# avrmf.net
KiCad netlist of a schematic drawn in EAGLE
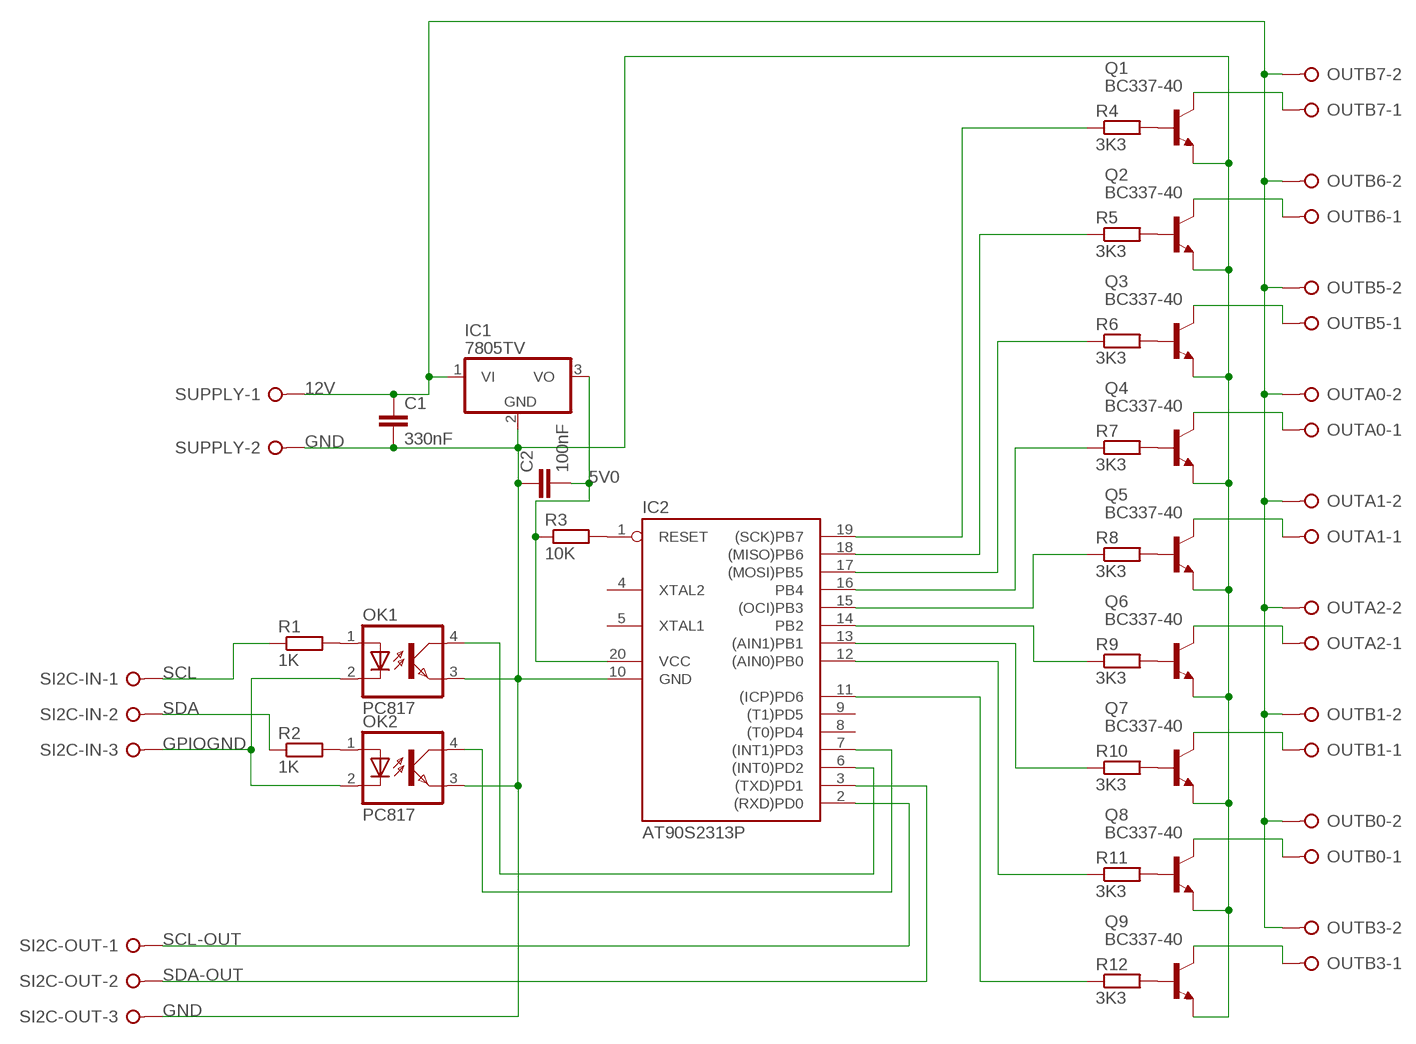
[diagram p0: schematic, sheet 1]

(export (version "E")
  (design (tool "Eeschema 10.0.6"))
  (components
    (comp (ref "C1")
      (value "330nF")
      (footprint "eagle-import:C2.5-3")
      (libsource (lib "eagle-import") (part "C2,5-3"))
    )
    (comp (ref "C2")
      (value "100nF")
      (footprint "eagle-import:C2.5-3")
      (libsource (lib "eagle-import") (part "C2,5-3"))
    )
    (comp (ref "IC1")
      (value "7805TV")
      (footprint "eagle-import:TO220V")
      (libsource (lib "eagle-import") (part "78TV05"))
    )
    (comp (ref "IC2")
      (value "AT90S2313P")
      (footprint "eagle-import:DIL20")
      (libsource (lib "eagle-import") (part "AT90S2313P"))
    )
    (comp (ref "OK1")
      (value "PC817")
      (footprint "eagle-import:DIL04")
      (fields (field (name "MPN") "PC817X4J000F"))
      (libsource (lib "eagle-import") (part "PC817"))
    )
    (comp (ref "OK2")
      (value "PC817")
      (footprint "eagle-import:DIL04")
      (fields (field (name "MPN") "PC817X4J000F"))
      (libsource (lib "eagle-import") (part "PC817"))
    )
    (comp (ref "OUTA0")
      (value "W237-02P")
      (footprint "eagle-import:W237-132")
      (libsource (lib "eagle-import") (part "W237-02P"))
    )
    (comp (ref "OUTA1")
      (value "W237-02P")
      (footprint "eagle-import:W237-132")
      (libsource (lib "eagle-import") (part "W237-02P"))
    )
    (comp (ref "OUTA2")
      (value "W237-02P")
      (footprint "eagle-import:W237-132")
      (libsource (lib "eagle-import") (part "W237-02P"))
    )
    (comp (ref "OUTB0")
      (value "W237-02P")
      (footprint "eagle-import:W237-132")
      (libsource (lib "eagle-import") (part "W237-02P"))
    )
    (comp (ref "OUTB1")
      (value "W237-02P")
      (footprint "eagle-import:W237-132")
      (libsource (lib "eagle-import") (part "W237-02P"))
    )
    (comp (ref "OUTB3")
      (value "W237-02P")
      (footprint "eagle-import:W237-132")
      (libsource (lib "eagle-import") (part "W237-02P"))
    )
    (comp (ref "OUTB5")
      (value "W237-02P")
      (footprint "eagle-import:W237-132")
      (libsource (lib "eagle-import") (part "W237-02P"))
    )
    (comp (ref "OUTB6")
      (value "W237-02P")
      (footprint "eagle-import:W237-132")
      (libsource (lib "eagle-import") (part "W237-02P"))
    )
    (comp (ref "OUTB7")
      (value "W237-02P")
      (footprint "eagle-import:W237-132")
      (libsource (lib "eagle-import") (part "W237-02P"))
    )
    (comp (ref "Q1")
      (value "BC337-40")
      (footprint "eagle-import:TO92")
      (libsource (lib "eagle-import") (part "BC337-40"))
    )
    (comp (ref "Q2")
      (value "BC337-40")
      (footprint "eagle-import:TO92")
      (libsource (lib "eagle-import") (part "BC337-40"))
    )
    (comp (ref "Q3")
      (value "BC337-40")
      (footprint "eagle-import:TO92")
      (libsource (lib "eagle-import") (part "BC337-40"))
    )
    (comp (ref "Q4")
      (value "BC337-40")
      (footprint "eagle-import:TO92")
      (libsource (lib "eagle-import") (part "BC337-40"))
    )
    (comp (ref "Q5")
      (value "BC337-40")
      (footprint "eagle-import:TO92")
      (libsource (lib "eagle-import") (part "BC337-40"))
    )
    (comp (ref "Q6")
      (value "BC337-40")
      (footprint "eagle-import:TO92")
      (libsource (lib "eagle-import") (part "BC337-40"))
    )
    (comp (ref "Q7")
      (value "BC337-40")
      (footprint "eagle-import:TO92")
      (libsource (lib "eagle-import") (part "BC337-40"))
    )
    (comp (ref "Q8")
      (value "BC337-40")
      (footprint "eagle-import:TO92")
      (libsource (lib "eagle-import") (part "BC337-40"))
    )
    (comp (ref "Q9")
      (value "BC337-40")
      (footprint "eagle-import:TO92")
      (libsource (lib "eagle-import") (part "BC337-40"))
    )
    (comp (ref "R1")
      (value "1K")
      (footprint "eagle-import:0207_10")
      (libsource (lib "eagle-import") (part "R-EU_0207/10"))
    )
    (comp (ref "R2")
      (value "1K")
      (footprint "eagle-import:0207_10")
      (libsource (lib "eagle-import") (part "R-EU_0207/10"))
    )
    (comp (ref "R3")
      (value "10K")
      (footprint "eagle-import:0207_10")
      (libsource (lib "eagle-import") (part "R-EU_0207/10"))
    )
    (comp (ref "R4")
      (value "3K3")
      (footprint "eagle-import:0207_10")
      (libsource (lib "eagle-import") (part "R-EU_0207/10"))
    )
    (comp (ref "R5")
      (value "3K3")
      (footprint "eagle-import:0207_10")
      (libsource (lib "eagle-import") (part "R-EU_0207/10"))
    )
    (comp (ref "R6")
      (value "3K3")
      (footprint "eagle-import:0207_10")
      (libsource (lib "eagle-import") (part "R-EU_0207/10"))
    )
    (comp (ref "R7")
      (value "3K3")
      (footprint "eagle-import:0207_10")
      (libsource (lib "eagle-import") (part "R-EU_0207/10"))
    )
    (comp (ref "R8")
      (value "3K3")
      (footprint "eagle-import:0207_10")
      (libsource (lib "eagle-import") (part "R-EU_0207/10"))
    )
    (comp (ref "R9")
      (value "3K3")
      (footprint "eagle-import:0207_10")
      (libsource (lib "eagle-import") (part "R-EU_0207/10"))
    )
    (comp (ref "R10")
      (value "3K3")
      (footprint "eagle-import:0207_10")
      (libsource (lib "eagle-import") (part "R-EU_0207/10"))
    )
    (comp (ref "R11")
      (value "3K3")
      (footprint "eagle-import:0207_10")
      (libsource (lib "eagle-import") (part "R-EU_0207/10"))
    )
    (comp (ref "R12")
      (value "3K3")
      (footprint "eagle-import:0207_10")
      (libsource (lib "eagle-import") (part "R-EU_0207/10"))
    )
    (comp (ref "SI2C-IN")
      (value "W237-3E")
      (footprint "eagle-import:W237-3E")
      (libsource (lib "eagle-import") (part "W237-3E"))
    )
    (comp (ref "SI2C-OUT")
      (value "W237-3E")
      (footprint "eagle-import:W237-3E")
      (libsource (lib "eagle-import") (part "W237-3E"))
    )
    (comp (ref "SUPPLY")
      (value "W237-02P")
      (footprint "eagle-import:W237-132")
      (libsource (lib "eagle-import") (part "W237-02P"))
    )
  )
  (nets
    (net (code "1") (name "/5V0") (class "Default")
      (node (ref "C2") (pin "2") (pinfunction "2_2") (pintype "passive"))
      (node (ref "IC1") (pin "3") (pinfunction "VO_3") (pintype "passive"))
      (node (ref "IC2") (pin "20") (pinfunction "VCC_20") (pintype "power_in"))
      (node (ref "R3") (pin "1") (pinfunction "1_1") (pintype "passive"))
    )
    (net (code "2") (name "/12V") (class "Default")
      (node (ref "C1") (pin "1") (pinfunction "1_1") (pintype "passive"))
      (node (ref "IC1") (pin "1") (pinfunction "VI_1") (pintype "input"))
      (node (ref "OUTA0") (pin "2") (pinfunction "KL_2") (pintype "passive"))
      (node (ref "OUTA1") (pin "2") (pinfunction "KL_2") (pintype "passive"))
      (node (ref "OUTA2") (pin "2") (pinfunction "KL_2") (pintype "passive"))
      (node (ref "OUTB0") (pin "2") (pinfunction "KL_2") (pintype "passive"))
      (node (ref "OUTB1") (pin "2") (pinfunction "KL_2") (pintype "passive"))
      (node (ref "OUTB3") (pin "2") (pinfunction "KL_2") (pintype "passive"))
      (node (ref "OUTB5") (pin "2") (pinfunction "KL_2") (pintype "passive"))
      (node (ref "OUTB6") (pin "2") (pinfunction "KL_2") (pintype "passive"))
      (node (ref "OUTB7") (pin "2") (pinfunction "KL_2") (pintype "passive"))
      (node (ref "SUPPLY") (pin "1") (pinfunction "KL_1") (pintype "passive"))
    )
    (net (code "3") (name "/GND") (class "Default")
      (node (ref "C1") (pin "2") (pinfunction "2_2") (pintype "passive"))
      (node (ref "C2") (pin "1") (pinfunction "1_1") (pintype "passive"))
      (node (ref "IC1") (pin "2") (pinfunction "GND_2") (pintype "passive"))
      (node (ref "IC2") (pin "10") (pinfunction "GND_10") (pintype "power_in"))
      (node (ref "OK1") (pin "3") (pinfunction "EMIT_3") (pintype "passive"))
      (node (ref "OK2") (pin "3") (pinfunction "EMIT_3") (pintype "passive"))
      (node (ref "Q1") (pin "1") (pinfunction "E_1") (pintype "passive"))
      (node (ref "Q2") (pin "1") (pinfunction "E_1") (pintype "passive"))
      (node (ref "Q3") (pin "1") (pinfunction "E_1") (pintype "passive"))
      (node (ref "Q4") (pin "1") (pinfunction "E_1") (pintype "passive"))
      (node (ref "Q5") (pin "1") (pinfunction "E_1") (pintype "passive"))
      (node (ref "Q6") (pin "1") (pinfunction "E_1") (pintype "passive"))
      (node (ref "Q7") (pin "1") (pinfunction "E_1") (pintype "passive"))
      (node (ref "Q8") (pin "1") (pinfunction "E_1") (pintype "passive"))
      (node (ref "Q9") (pin "1") (pinfunction "E_1") (pintype "passive"))
      (node (ref "SI2C-OUT") (pin "3") (pinfunction "KL_3") (pintype "passive"))
      (node (ref "SUPPLY") (pin "2") (pinfunction "KL_2") (pintype "passive"))
    )
    (net (code "4") (name "/GPIOGND") (class "Default")
      (node (ref "OK1") (pin "2") (pinfunction "C_2") (pintype "passive"))
      (node (ref "OK2") (pin "2") (pinfunction "C_2") (pintype "passive"))
      (node (ref "SI2C-IN") (pin "3") (pinfunction "KL_3") (pintype "passive"))
    )
    (net (code "5") (name "/SCL") (class "Default")
      (node (ref "R1") (pin "1") (pinfunction "1_1") (pintype "passive"))
      (node (ref "SI2C-IN") (pin "1") (pinfunction "KL_1") (pintype "passive"))
    )
    (net (code "6") (name "/SCL-OUT") (class "Default")
      (node (ref "IC2") (pin "2") (pinfunction "(RXD)PD0_2") (pintype "bidirectional"))
      (node (ref "SI2C-OUT") (pin "1") (pinfunction "KL_1") (pintype "passive"))
    )
    (net (code "7") (name "/SDA") (class "Default")
      (node (ref "R2") (pin "1") (pinfunction "1_1") (pintype "passive"))
      (node (ref "SI2C-IN") (pin "2") (pinfunction "KL_2") (pintype "passive"))
    )
    (net (code "8") (name "/SDA-OUT") (class "Default")
      (node (ref "IC2") (pin "3") (pinfunction "(TXD)PD1_3") (pintype "bidirectional"))
      (node (ref "SI2C-OUT") (pin "2") (pinfunction "KL_2") (pintype "passive"))
    )
    (net (code "9") (name "Net-(IC2-(AIN0)PB0)") (class "Default")
      (node (ref "IC2") (pin "12") (pinfunction "(AIN0)PB0_12") (pintype "bidirectional"))
      (node (ref "R11") (pin "1") (pinfunction "1_1") (pintype "passive"))
    )
    (net (code "10") (name "Net-(IC2-(AIN1)PB1)") (class "Default")
      (node (ref "IC2") (pin "13") (pinfunction "(AIN1)PB1_13") (pintype "bidirectional"))
      (node (ref "R10") (pin "1") (pinfunction "1_1") (pintype "passive"))
    )
    (net (code "11") (name "Net-(IC2-(ICP)PD6)") (class "Default")
      (node (ref "IC2") (pin "11") (pinfunction "(ICP)PD6_11") (pintype "bidirectional"))
      (node (ref "R12") (pin "1") (pinfunction "1_1") (pintype "passive"))
    )
    (net (code "12") (name "Net-(IC2-(INT0)PD2)") (class "Default")
      (node (ref "IC2") (pin "6") (pinfunction "(INT0)PD2_6") (pintype "bidirectional"))
      (node (ref "OK1") (pin "4") (pinfunction "COL_4") (pintype "passive"))
    )
    (net (code "13") (name "Net-(IC2-(INT1)PD3)") (class "Default")
      (node (ref "IC2") (pin "7") (pinfunction "(INT1)PD3_7") (pintype "bidirectional"))
      (node (ref "OK2") (pin "4") (pinfunction "COL_4") (pintype "passive"))
    )
    (net (code "14") (name "Net-(IC2-(MISO)PB6)") (class "Default")
      (node (ref "IC2") (pin "18") (pinfunction "(MISO)PB6_18") (pintype "bidirectional"))
      (node (ref "R5") (pin "1") (pinfunction "1_1") (pintype "passive"))
    )
    (net (code "15") (name "Net-(IC2-(MOSI)PB5)") (class "Default")
      (node (ref "IC2") (pin "17") (pinfunction "(MOSI)PB5_17") (pintype "bidirectional"))
      (node (ref "R6") (pin "1") (pinfunction "1_1") (pintype "passive"))
    )
    (net (code "16") (name "Net-(IC2-(OCI)PB3)") (class "Default")
      (node (ref "IC2") (pin "15") (pinfunction "(OCI)PB3_15") (pintype "bidirectional"))
      (node (ref "R8") (pin "1") (pinfunction "1_1") (pintype "passive"))
    )
    (net (code "17") (name "Net-(IC2-(SCK)PB7)") (class "Default")
      (node (ref "IC2") (pin "19") (pinfunction "(SCK)PB7_19") (pintype "bidirectional"))
      (node (ref "R4") (pin "1") (pinfunction "1_1") (pintype "passive"))
    )
    (net (code "18") (name "Net-(IC2-PB2)") (class "Default")
      (node (ref "IC2") (pin "14") (pinfunction "PB2_14") (pintype "bidirectional"))
      (node (ref "R9") (pin "1") (pinfunction "1_1") (pintype "passive"))
    )
    (net (code "19") (name "Net-(IC2-PB4)") (class "Default")
      (node (ref "IC2") (pin "16") (pinfunction "PB4_16") (pintype "bidirectional"))
      (node (ref "R7") (pin "1") (pinfunction "1_1") (pintype "passive"))
    )
    (net (code "20") (name "Net-(IC2-RESET)") (class "Default")
      (node (ref "IC2") (pin "1") (pinfunction "RESET_1") (pintype "bidirectional"))
      (node (ref "R3") (pin "2") (pinfunction "2_2") (pintype "passive"))
    )
    (net (code "21") (name "Net-(OK1-A)") (class "Default")
      (node (ref "OK1") (pin "1") (pinfunction "A_1") (pintype "passive"))
      (node (ref "R1") (pin "2") (pinfunction "2_2") (pintype "passive"))
    )
    (net (code "22") (name "Net-(OK2-A)") (class "Default")
      (node (ref "OK2") (pin "1") (pinfunction "A_1") (pintype "passive"))
      (node (ref "R2") (pin "2") (pinfunction "2_2") (pintype "passive"))
    )
    (net (code "23") (name "Net-(OUTA0A-KL)") (class "Default")
      (node (ref "OUTA0") (pin "1") (pinfunction "KL_1") (pintype "passive"))
      (node (ref "Q4") (pin "3") (pinfunction "C_3") (pintype "passive"))
    )
    (net (code "24") (name "Net-(OUTA1A-KL)") (class "Default")
      (node (ref "OUTA1") (pin "1") (pinfunction "KL_1") (pintype "passive"))
      (node (ref "Q5") (pin "3") (pinfunction "C_3") (pintype "passive"))
    )
    (net (code "25") (name "Net-(OUTA2A-KL)") (class "Default")
      (node (ref "OUTA2") (pin "1") (pinfunction "KL_1") (pintype "passive"))
      (node (ref "Q6") (pin "3") (pinfunction "C_3") (pintype "passive"))
    )
    (net (code "26") (name "Net-(OUTB0A-KL)") (class "Default")
      (node (ref "OUTB0") (pin "1") (pinfunction "KL_1") (pintype "passive"))
      (node (ref "Q8") (pin "3") (pinfunction "C_3") (pintype "passive"))
    )
    (net (code "27") (name "Net-(OUTB1A-KL)") (class "Default")
      (node (ref "OUTB1") (pin "1") (pinfunction "KL_1") (pintype "passive"))
      (node (ref "Q7") (pin "3") (pinfunction "C_3") (pintype "passive"))
    )
    (net (code "28") (name "Net-(OUTB3A-KL)") (class "Default")
      (node (ref "OUTB3") (pin "1") (pinfunction "KL_1") (pintype "passive"))
      (node (ref "Q9") (pin "3") (pinfunction "C_3") (pintype "passive"))
    )
    (net (code "29") (name "Net-(OUTB5A-KL)") (class "Default")
      (node (ref "OUTB5") (pin "1") (pinfunction "KL_1") (pintype "passive"))
      (node (ref "Q3") (pin "3") (pinfunction "C_3") (pintype "passive"))
    )
    (net (code "30") (name "Net-(OUTB6A-KL)") (class "Default")
      (node (ref "OUTB6") (pin "1") (pinfunction "KL_1") (pintype "passive"))
      (node (ref "Q2") (pin "3") (pinfunction "C_3") (pintype "passive"))
    )
    (net (code "31") (name "Net-(OUTB7A-KL)") (class "Default")
      (node (ref "OUTB7") (pin "1") (pinfunction "KL_1") (pintype "passive"))
      (node (ref "Q1") (pin "3") (pinfunction "C_3") (pintype "passive"))
    )
    (net (code "32") (name "Net-(Q1-B)") (class "Default")
      (node (ref "Q1") (pin "2") (pinfunction "B_2") (pintype "passive"))
      (node (ref "R4") (pin "2") (pinfunction "2_2") (pintype "passive"))
    )
    (net (code "33") (name "Net-(Q2-B)") (class "Default")
      (node (ref "Q2") (pin "2") (pinfunction "B_2") (pintype "passive"))
      (node (ref "R5") (pin "2") (pinfunction "2_2") (pintype "passive"))
    )
    (net (code "34") (name "Net-(Q3-B)") (class "Default")
      (node (ref "Q3") (pin "2") (pinfunction "B_2") (pintype "passive"))
      (node (ref "R6") (pin "2") (pinfunction "2_2") (pintype "passive"))
    )
    (net (code "35") (name "Net-(Q4-B)") (class "Default")
      (node (ref "Q4") (pin "2") (pinfunction "B_2") (pintype "passive"))
      (node (ref "R7") (pin "2") (pinfunction "2_2") (pintype "passive"))
    )
    (net (code "36") (name "Net-(Q5-B)") (class "Default")
      (node (ref "Q5") (pin "2") (pinfunction "B_2") (pintype "passive"))
      (node (ref "R8") (pin "2") (pinfunction "2_2") (pintype "passive"))
    )
    (net (code "37") (name "Net-(Q6-B)") (class "Default")
      (node (ref "Q6") (pin "2") (pinfunction "B_2") (pintype "passive"))
      (node (ref "R9") (pin "2") (pinfunction "2_2") (pintype "passive"))
    )
    (net (code "38") (name "Net-(Q7-B)") (class "Default")
      (node (ref "Q7") (pin "2") (pinfunction "B_2") (pintype "passive"))
      (node (ref "R10") (pin "2") (pinfunction "2_2") (pintype "passive"))
    )
    (net (code "39") (name "Net-(Q8-B)") (class "Default")
      (node (ref "Q8") (pin "2") (pinfunction "B_2") (pintype "passive"))
      (node (ref "R11") (pin "2") (pinfunction "2_2") (pintype "passive"))
    )
    (net (code "40") (name "Net-(Q9-B)") (class "Default")
      (node (ref "Q9") (pin "2") (pinfunction "B_2") (pintype "passive"))
      (node (ref "R12") (pin "2") (pinfunction "2_2") (pintype "passive"))
    )
    (net (code "41") (name "unconnected-(IC2-(T0)PD4-Pad8)") (class "Default")
      (node (ref "IC2") (pin "8") (pinfunction "(T0)PD4_8") (pintype "bidirectional"))
    )
    (net (code "42") (name "unconnected-(IC2-(T1)PD5-Pad9)") (class "Default")
      (node (ref "IC2") (pin "9") (pinfunction "(T1)PD5_9") (pintype "bidirectional"))
    )
    (net (code "43") (name "unconnected-(IC2-XTAL1-Pad5)") (class "Default")
      (node (ref "IC2") (pin "5") (pinfunction "XTAL1_5") (pintype "bidirectional"))
    )
    (net (code "44") (name "unconnected-(IC2-XTAL2-Pad4)") (class "Default")
      (node (ref "IC2") (pin "4") (pinfunction "XTAL2_4") (pintype "bidirectional"))
    )
  )
)
